# ControlModule.net
KiCad netlist of a schematic drawn in EAGLE
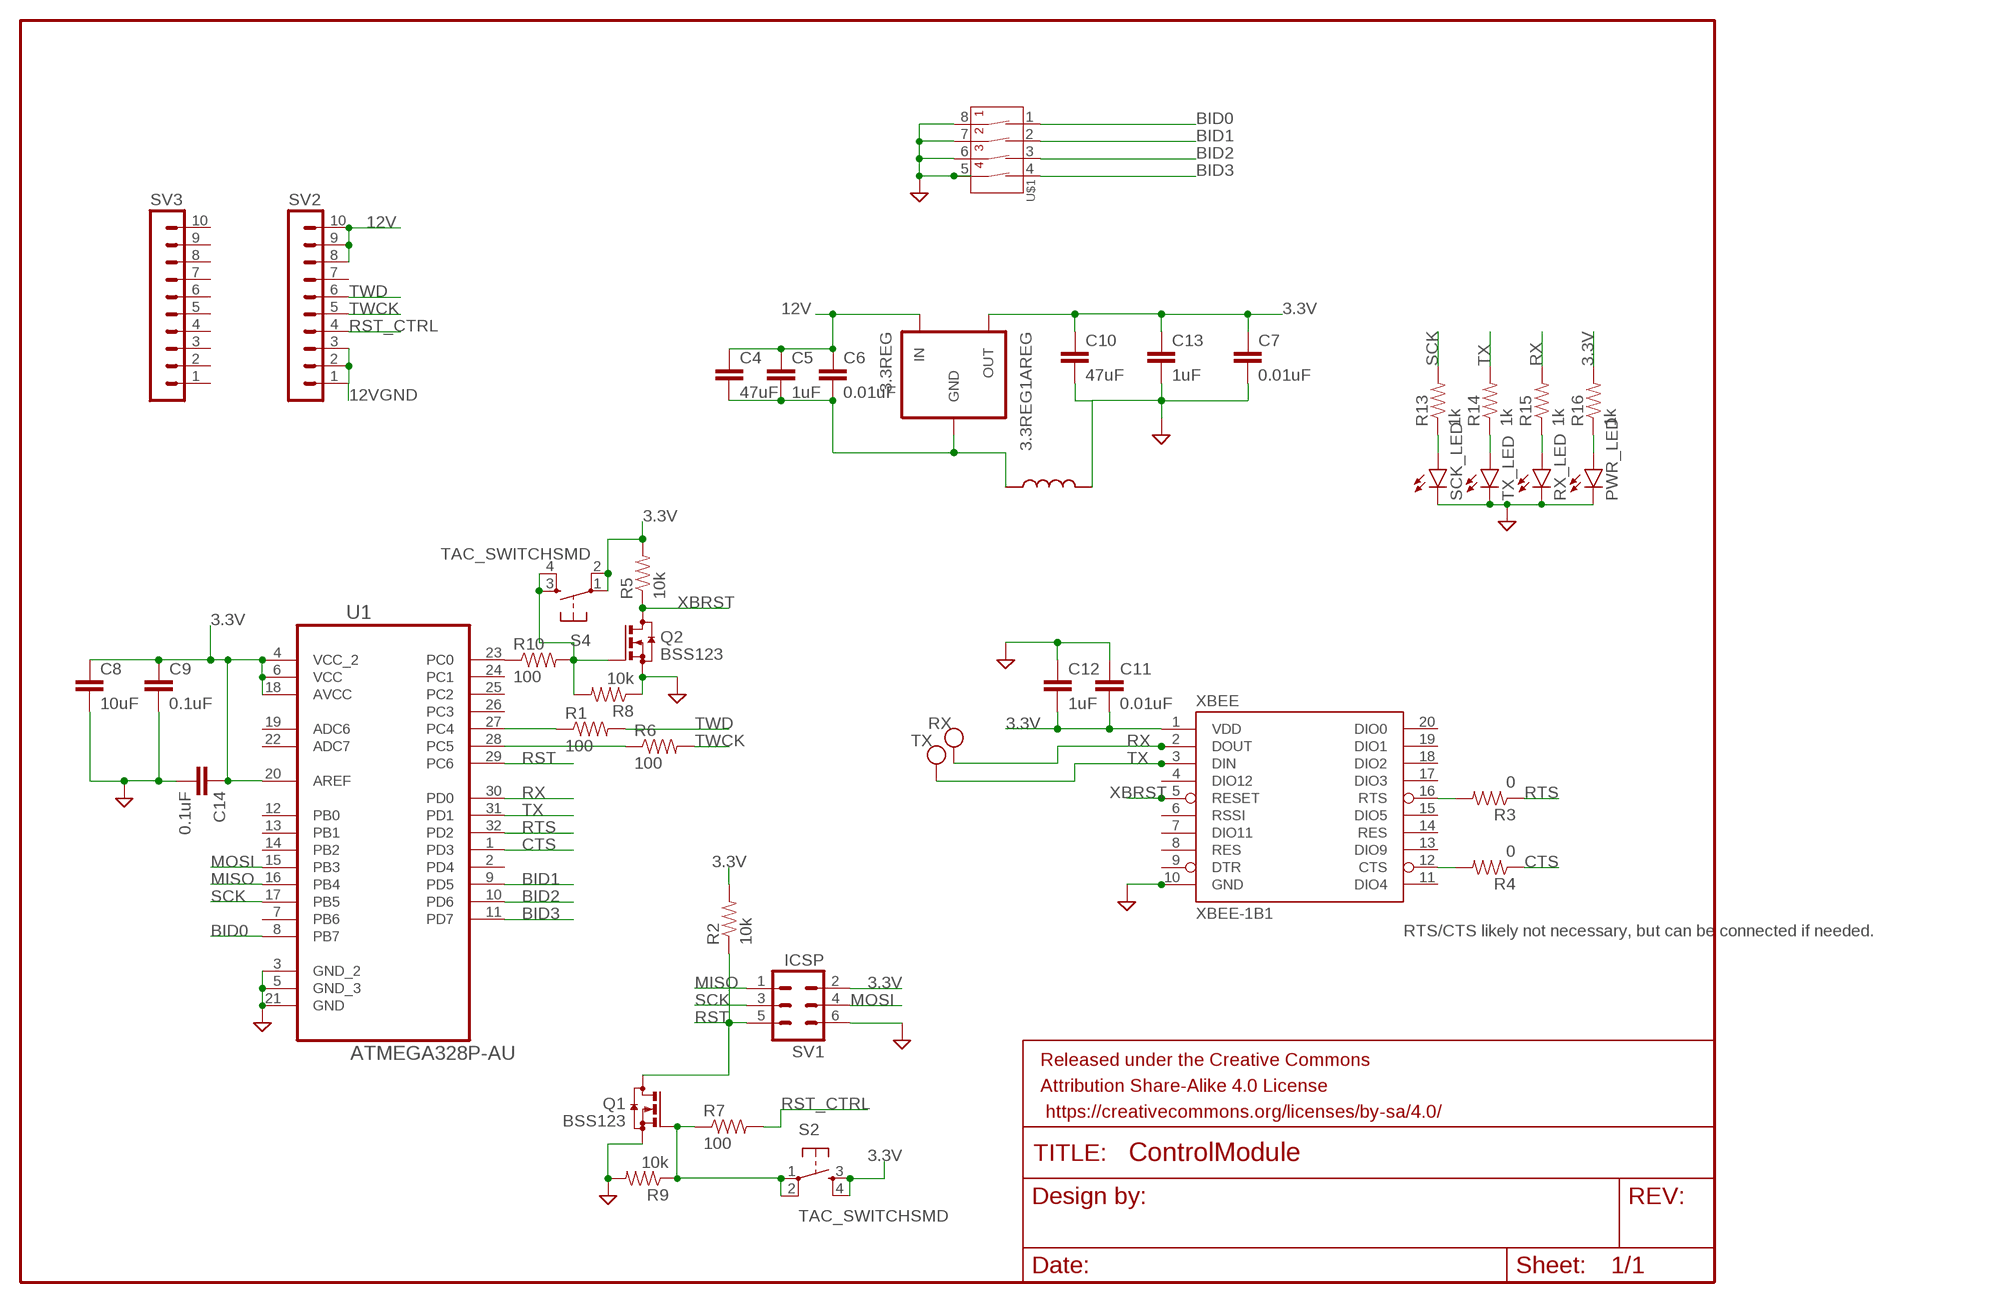
[diagram p0: schematic, sheet 1]

(export (version "E")
  (design (tool "Eeschema 10.0.6"))
  (components
    (comp (ref "3.3REG")
      (value "3.3REG1AREG")
      (footprint "eagle-import:DPAK")
      (libsource (lib "eagle-import") (part "3.3REG1AREG"))
    )
    (comp (ref "C4")
      (value "47uF")
      (footprint "eagle-import:1206")
      (libsource (lib "eagle-import") (part "CAP1206"))
    )
    (comp (ref "C5")
      (value "1uF")
      (footprint "eagle-import:0805")
      (libsource (lib "eagle-import") (part "CAP0805"))
    )
    (comp (ref "C6")
      (value "0.01uF")
      (footprint "eagle-import:0805")
      (libsource (lib "eagle-import") (part "CAP0805"))
    )
    (comp (ref "C7")
      (value "0.01uF")
      (footprint "eagle-import:0805")
      (libsource (lib "eagle-import") (part "CAP0805"))
    )
    (comp (ref "C8")
      (value "10uF")
      (footprint "eagle-import:0805")
      (libsource (lib "eagle-import") (part "CAP0805"))
    )
    (comp (ref "C9")
      (value "0.1uF")
      (footprint "eagle-import:0805")
      (libsource (lib "eagle-import") (part "CAP0805"))
    )
    (comp (ref "C10")
      (value "47uF")
      (footprint "eagle-import:1206")
      (libsource (lib "eagle-import") (part "CAP1206"))
    )
    (comp (ref "C11")
      (value "0.01uF")
      (footprint "eagle-import:0805")
      (libsource (lib "eagle-import") (part "CAP0805"))
    )
    (comp (ref "C12")
      (value "1uF")
      (footprint "eagle-import:0805")
      (libsource (lib "eagle-import") (part "CAP0805"))
    )
    (comp (ref "C13")
      (value "1uF")
      (footprint "eagle-import:0805")
      (libsource (lib "eagle-import") (part "CAP0805"))
    )
    (comp (ref "C14")
      (value "0.1uF")
      (footprint "eagle-import:0805")
      (libsource (lib "eagle-import") (part "CAP0805"))
    )
    (comp (ref "FRAME1")
      (value "FRAME-LETTER")
      (footprint "eagle-import:CREATIVE_COMMONS")
      (libsource (lib "eagle-import") (part "FRAME-LETTER"))
    )
    (comp (ref "PWR_LED")
      (value "LED1206")
      (footprint "eagle-import:LED-1206")
      (libsource (lib "eagle-import") (part "LED1206"))
    )
    (comp (ref "Q1")
      (value "BSS123")
      (footprint "eagle-import:SOT23")
      (libsource (lib "eagle-import") (part "BSS123"))
    )
    (comp (ref "Q2")
      (value "BSS123")
      (footprint "eagle-import:SOT23")
      (libsource (lib "eagle-import") (part "BSS123"))
    )
    (comp (ref "R1")
      (value "100")
      (footprint "eagle-import:0805")
      (libsource (lib "eagle-import") (part "RESISTOR0805-RES"))
    )
    (comp (ref "R2")
      (value "10k")
      (footprint "eagle-import:0805")
      (libsource (lib "eagle-import") (part "RESISTOR0805-RES"))
    )
    (comp (ref "R3")
      (value "0")
      (footprint "eagle-import:0805")
      (libsource (lib "eagle-import") (part "RESISTOR0805-RES"))
    )
    (comp (ref "R4")
      (value "0")
      (footprint "eagle-import:0805")
      (libsource (lib "eagle-import") (part "RESISTOR0805-RES"))
    )
    (comp (ref "R5")
      (value "10k")
      (footprint "eagle-import:0805")
      (libsource (lib "eagle-import") (part "RESISTOR0805-RES"))
    )
    (comp (ref "R6")
      (value "100")
      (footprint "eagle-import:0805")
      (libsource (lib "eagle-import") (part "RESISTOR0805-RES"))
    )
    (comp (ref "R7")
      (value "100")
      (footprint "eagle-import:0805")
      (libsource (lib "eagle-import") (part "RESISTOR0805-RES"))
    )
    (comp (ref "R8")
      (value "10k")
      (footprint "eagle-import:0805")
      (libsource (lib "eagle-import") (part "RESISTOR0805-RES"))
    )
    (comp (ref "R9")
      (value "10k")
      (footprint "eagle-import:0805")
      (libsource (lib "eagle-import") (part "RESISTOR0805-RES"))
    )
    (comp (ref "R10")
      (value "100")
      (footprint "eagle-import:0805")
      (libsource (lib "eagle-import") (part "RESISTOR0805-RES"))
    )
    (comp (ref "R13")
      (value "1k")
      (footprint "eagle-import:0805")
      (libsource (lib "eagle-import") (part "RESISTOR0805-RES"))
    )
    (comp (ref "R14")
      (value "1k")
      (footprint "eagle-import:0805")
      (libsource (lib "eagle-import") (part "RESISTOR0805-RES"))
    )
    (comp (ref "R15")
      (value "1k")
      (footprint "eagle-import:0805")
      (libsource (lib "eagle-import") (part "RESISTOR0805-RES"))
    )
    (comp (ref "R16")
      (value "1k")
      (footprint "eagle-import:0805")
      (libsource (lib "eagle-import") (part "RESISTOR0805-RES"))
    )
    (comp (ref "RX")
      (value "TEST_PT")
      (footprint "eagle-import:TESTING_PT")
      (libsource (lib "eagle-import") (part "TEST_PT"))
    )
    (comp (ref "RX_LED")
      (value "LED1206")
      (footprint "eagle-import:LED-1206")
      (libsource (lib "eagle-import") (part "LED1206"))
    )
    (comp (ref "S2")
      (value "TAC_SWITCHSMD")
      (footprint "eagle-import:TACTILE-SWITCH-SMD")
      (libsource (lib "eagle-import") (part "TAC_SWITCHSMD"))
    )
    (comp (ref "S4")
      (value "TAC_SWITCHSMD")
      (footprint "eagle-import:TACTILE-SWITCH-SMD")
      (libsource (lib "eagle-import") (part "TAC_SWITCHSMD"))
    )
    (comp (ref "SCK_LED")
      (value "LED1206")
      (footprint "eagle-import:LED-1206")
      (libsource (lib "eagle-import") (part "LED1206"))
    )
    (comp (ref "SV1")
      (value "ICSP")
      (footprint "eagle-import:MA03-2")
      (libsource (lib "eagle-import") (part "MA03-2"))
    )
    (comp (ref "SV2")
      (value "MA10-1W")
      (footprint "eagle-import:MA10-1W")
      (libsource (lib "eagle-import") (part "MA10-1W"))
    )
    (comp (ref "SV3")
      (value "MA10-1W")
      (footprint "eagle-import:MA10-1W")
      (libsource (lib "eagle-import") (part "MA10-1W"))
    )
    (comp (ref "TX")
      (value "TEST_PT")
      (footprint "eagle-import:TESTING_PT")
      (libsource (lib "eagle-import") (part "TEST_PT"))
    )
    (comp (ref "TX_LED")
      (value "LED1206")
      (footprint "eagle-import:LED-1206")
      (libsource (lib "eagle-import") (part "LED1206"))
    )
    (comp (ref "U$1")
      (value "4-POS-DIP")
      (footprint "eagle-import:4-POS-DIP-SMD")
      (libsource (lib "eagle-import") (part "4-POS-DIP"))
    )
    (comp (ref "U$2")
      (value "INDUCTOR")
      (footprint "eagle-import:0805")
      (libsource (lib "eagle-import") (part "INDUCTOR"))
    )
    (comp (ref "U1")
      (value "ATMEGA328P-AU")
      (footprint "eagle-import:QFP80P900X900X120-32N")
      (libsource (lib "eagle-import") (part "ATMEGA328P-AU"))
    )
    (comp (ref "XBEE")
      (value "XBEE-1B1")
      (footprint "eagle-import:XBEE-1")
      (libsource (lib "eagle-import") (part "XBEE-1B1"))
    )
  )
  (nets
    (net (code "1") (name "/3.3V") (class "Default")
      (node (ref "3.3REG") (pin "SOURCE") (pinfunction "OUT_SOURCE") (pintype "bidirectional"))
      (node (ref "C10") (pin "1") (pinfunction "1_1") (pintype "passive"))
      (node (ref "C11") (pin "2") (pinfunction "2_2") (pintype "passive"))
      (node (ref "C12") (pin "2") (pinfunction "2_2") (pintype "passive"))
      (node (ref "C13") (pin "1") (pinfunction "1_1") (pintype "passive"))
      (node (ref "C14") (pin "1") (pinfunction "1_1") (pintype "passive"))
      (node (ref "C7") (pin "1") (pinfunction "1_1") (pintype "passive"))
      (node (ref "C8") (pin "1") (pinfunction "1_1") (pintype "passive"))
      (node (ref "C9") (pin "1") (pinfunction "1_1") (pintype "passive"))
      (node (ref "R16") (pin "2") (pinfunction "2_2") (pintype "passive"))
      (node (ref "R2") (pin "2") (pinfunction "2_2") (pintype "passive"))
      (node (ref "R5") (pin "2") (pinfunction "2_2") (pintype "passive"))
      (node (ref "S2") (pin "3") (pinfunction "3_3") (pintype "passive"))
      (node (ref "S2") (pin "4") (pinfunction "4_4") (pintype "passive"))
      (node (ref "S4") (pin "1") (pinfunction "1_1") (pintype "passive"))
      (node (ref "S4") (pin "2") (pinfunction "2_2") (pintype "passive"))
      (node (ref "SV1") (pin "2") (pinfunction "2_2") (pintype "passive"))
      (node (ref "U1") (pin "18") (pinfunction "AVCC_18") (pintype "power_in"))
      (node (ref "U1") (pin "20") (pinfunction "AREF_20") (pintype "input"))
      (node (ref "U1") (pin "4") (pinfunction "VCC_2_4") (pintype "power_in"))
      (node (ref "U1") (pin "6") (pinfunction "VCC_6") (pintype "power_in"))
      (node (ref "XBEE") (pin "1") (pinfunction "VDD_1") (pintype "power_in"))
    )
    (net (code "2") (name "/12V") (class "Default")
      (node (ref "3.3REG") (pin "GATE") (pinfunction "IN_GATE") (pintype "input"))
      (node (ref "C4") (pin "1") (pinfunction "1_1") (pintype "passive"))
      (node (ref "C5") (pin "1") (pinfunction "1_1") (pintype "passive"))
      (node (ref "C6") (pin "1") (pinfunction "1_1") (pintype "passive"))
      (node (ref "SV2") (pin "10") (pinfunction "10_10") (pintype "passive"))
      (node (ref "SV2") (pin "8") (pinfunction "8_8") (pintype "passive"))
      (node (ref "SV2") (pin "9") (pinfunction "9_9") (pintype "passive"))
    )
    (net (code "3") (name "/12VGND") (class "Default")
      (node (ref "3.3REG") (pin "DRAIN") (pinfunction "GND_DRAIN") (pintype "bidirectional"))
      (node (ref "C4") (pin "2") (pinfunction "2_2") (pintype "passive"))
      (node (ref "C5") (pin "2") (pinfunction "2_2") (pintype "passive"))
      (node (ref "C6") (pin "2") (pinfunction "2_2") (pintype "passive"))
      (node (ref "SV2") (pin "1") (pinfunction "1_1") (pintype "passive"))
      (node (ref "SV2") (pin "2") (pinfunction "2_2") (pintype "passive"))
      (node (ref "SV2") (pin "3") (pinfunction "3_3") (pintype "passive"))
      (node (ref "U$2") (pin "1") (pinfunction "P$1_1") (pintype "bidirectional"))
    )
    (net (code "4") (name "/BID0") (class "Default")
      (node (ref "U$1") (pin "1") (pinfunction "1A_1") (pintype "bidirectional"))
      (node (ref "U1") (pin "8") (pinfunction "PB7_8") (pintype "bidirectional"))
    )
    (net (code "5") (name "/BID1") (class "Default")
      (node (ref "U$1") (pin "2") (pinfunction "2A_2") (pintype "bidirectional"))
      (node (ref "U1") (pin "9") (pinfunction "PD5_9") (pintype "bidirectional"))
    )
    (net (code "6") (name "/BID2") (class "Default")
      (node (ref "U$1") (pin "3") (pinfunction "3A_3") (pintype "bidirectional"))
      (node (ref "U1") (pin "10") (pinfunction "PD6_10") (pintype "bidirectional"))
    )
    (net (code "7") (name "/BID3") (class "Default")
      (node (ref "U$1") (pin "4") (pinfunction "4A_4") (pintype "bidirectional"))
      (node (ref "U1") (pin "11") (pinfunction "PD7_11") (pintype "bidirectional"))
    )
    (net (code "8") (name "/CTS") (class "Default")
      (node (ref "R4") (pin "1") (pinfunction "1_1") (pintype "passive"))
      (node (ref "U1") (pin "1") (pinfunction "PD3_1") (pintype "bidirectional"))
    )
    (net (code "9") (name "/MISO") (class "Default")
      (node (ref "SV1") (pin "1") (pinfunction "1_1") (pintype "passive"))
      (node (ref "U1") (pin "16") (pinfunction "PB4_16") (pintype "bidirectional"))
    )
    (net (code "10") (name "/MOSI") (class "Default")
      (node (ref "SV1") (pin "4") (pinfunction "4_4") (pintype "passive"))
      (node (ref "U1") (pin "15") (pinfunction "PB3_15") (pintype "bidirectional"))
    )
    (net (code "11") (name "/RST") (class "Default")
      (node (ref "Q1") (pin "3") (pinfunction "D_3") (pintype "passive"))
      (node (ref "R2") (pin "1") (pinfunction "1_1") (pintype "passive"))
      (node (ref "SV1") (pin "5") (pinfunction "5_5") (pintype "passive"))
      (node (ref "U1") (pin "29") (pinfunction "PC6_29") (pintype "bidirectional"))
    )
    (net (code "12") (name "/RST_CTRL") (class "Default")
      (node (ref "R7") (pin "2") (pinfunction "2_2") (pintype "passive"))
      (node (ref "SV2") (pin "4") (pinfunction "4_4") (pintype "passive"))
    )
    (net (code "13") (name "/RTS") (class "Default")
      (node (ref "R3") (pin "1") (pinfunction "1_1") (pintype "passive"))
      (node (ref "U1") (pin "32") (pinfunction "PD2_32") (pintype "bidirectional"))
    )
    (net (code "14") (name "/RX") (class "Default")
      (node (ref "R15") (pin "2") (pinfunction "2_2") (pintype "passive"))
      (node (ref "RX") (pin "P$1") (pinfunction "P$1_P$1") (pintype "bidirectional"))
      (node (ref "U1") (pin "30") (pinfunction "PD0_30") (pintype "bidirectional"))
      (node (ref "XBEE") (pin "2") (pinfunction "DOUT_2") (pintype "output"))
    )
    (net (code "15") (name "/SCK") (class "Default")
      (node (ref "R13") (pin "2") (pinfunction "2_2") (pintype "passive"))
      (node (ref "SV1") (pin "3") (pinfunction "3_3") (pintype "passive"))
      (node (ref "U1") (pin "17") (pinfunction "PB5_17") (pintype "bidirectional"))
    )
    (net (code "16") (name "/TWCK") (class "Default")
      (node (ref "R6") (pin "2") (pinfunction "2_2") (pintype "passive"))
      (node (ref "SV2") (pin "5") (pinfunction "5_5") (pintype "passive"))
    )
    (net (code "17") (name "/TWD") (class "Default")
      (node (ref "R1") (pin "2") (pinfunction "2_2") (pintype "passive"))
      (node (ref "SV2") (pin "6") (pinfunction "6_6") (pintype "passive"))
    )
    (net (code "18") (name "/TX") (class "Default")
      (node (ref "R14") (pin "2") (pinfunction "2_2") (pintype "passive"))
      (node (ref "TX") (pin "P$1") (pinfunction "P$1_P$1") (pintype "bidirectional"))
      (node (ref "U1") (pin "31") (pinfunction "PD1_31") (pintype "bidirectional"))
      (node (ref "XBEE") (pin "3") (pinfunction "DIN_3") (pintype "input"))
    )
    (net (code "19") (name "/XBRST") (class "Default")
      (node (ref "Q2") (pin "3") (pinfunction "D_3") (pintype "passive"))
      (node (ref "R5") (pin "1") (pinfunction "1_1") (pintype "passive"))
      (node (ref "XBEE") (pin "5") (pinfunction "RESET_5") (pintype "input"))
    )
    (net (code "20") (name "GND") (class "Default")
      (node (ref "C10") (pin "2") (pinfunction "2_2") (pintype "passive"))
      (node (ref "C11") (pin "1") (pinfunction "1_1") (pintype "passive"))
      (node (ref "C12") (pin "1") (pinfunction "1_1") (pintype "passive"))
      (node (ref "C13") (pin "2") (pinfunction "2_2") (pintype "passive"))
      (node (ref "C14") (pin "2") (pinfunction "2_2") (pintype "passive"))
      (node (ref "C7") (pin "2") (pinfunction "2_2") (pintype "passive"))
      (node (ref "C8") (pin "2") (pinfunction "2_2") (pintype "passive"))
      (node (ref "C9") (pin "2") (pinfunction "2_2") (pintype "passive"))
      (node (ref "PWR_LED") (pin "C") (pinfunction "C_C") (pintype "passive"))
      (node (ref "Q1") (pin "2") (pinfunction "S_2") (pintype "passive"))
      (node (ref "Q2") (pin "2") (pinfunction "S_2") (pintype "passive"))
      (node (ref "R8") (pin "1") (pinfunction "1_1") (pintype "passive"))
      (node (ref "R9") (pin "2") (pinfunction "2_2") (pintype "passive"))
      (node (ref "RX_LED") (pin "C") (pinfunction "C_C") (pintype "passive"))
      (node (ref "SCK_LED") (pin "C") (pinfunction "C_C") (pintype "passive"))
      (node (ref "SV1") (pin "6") (pinfunction "6_6") (pintype "passive"))
      (node (ref "TX_LED") (pin "C") (pinfunction "C_C") (pintype "passive"))
      (node (ref "U$1") (pin "5") (pinfunction "4B_5") (pintype "bidirectional"))
      (node (ref "U$1") (pin "6") (pinfunction "3B_6") (pintype "bidirectional"))
      (node (ref "U$1") (pin "7") (pinfunction "2B_7") (pintype "bidirectional"))
      (node (ref "U$1") (pin "8") (pinfunction "1B_8") (pintype "bidirectional"))
      (node (ref "U$2") (pin "2") (pinfunction "P$2_2") (pintype "bidirectional"))
      (node (ref "U1") (pin "21") (pinfunction "GND_21") (pintype "passive"))
      (node (ref "U1") (pin "3") (pinfunction "GND_2_3") (pintype "passive"))
      (node (ref "U1") (pin "5") (pinfunction "GND_3_5") (pintype "passive"))
      (node (ref "XBEE") (pin "10") (pinfunction "GND_10") (pintype "power_in"))
    )
    (net (code "21") (name "Net-(PWR_LED-PadA)") (class "Default")
      (node (ref "PWR_LED") (pin "A") (pinfunction "A_A") (pintype "passive"))
      (node (ref "R16") (pin "1") (pinfunction "1_1") (pintype "passive"))
    )
    (net (code "22") (name "Net-(Q1-G)") (class "Default")
      (node (ref "Q1") (pin "1") (pinfunction "G_1") (pintype "passive"))
      (node (ref "R7") (pin "1") (pinfunction "1_1") (pintype "passive"))
      (node (ref "R9") (pin "1") (pinfunction "1_1") (pintype "passive"))
      (node (ref "S2") (pin "1") (pinfunction "1_1") (pintype "passive"))
      (node (ref "S2") (pin "2") (pinfunction "2_2") (pintype "passive"))
    )
    (net (code "23") (name "Net-(Q2-G)") (class "Default")
      (node (ref "Q2") (pin "1") (pinfunction "G_1") (pintype "passive"))
      (node (ref "R10") (pin "2") (pinfunction "2_2") (pintype "passive"))
      (node (ref "R8") (pin "2") (pinfunction "2_2") (pintype "passive"))
      (node (ref "S4") (pin "3") (pinfunction "3_3") (pintype "passive"))
      (node (ref "S4") (pin "4") (pinfunction "4_4") (pintype "passive"))
    )
    (net (code "24") (name "Net-(R13-Pad1)") (class "Default")
      (node (ref "R13") (pin "1") (pinfunction "1_1") (pintype "passive"))
      (node (ref "SCK_LED") (pin "A") (pinfunction "A_A") (pintype "passive"))
    )
    (net (code "25") (name "Net-(R14-Pad1)") (class "Default")
      (node (ref "R14") (pin "1") (pinfunction "1_1") (pintype "passive"))
      (node (ref "TX_LED") (pin "A") (pinfunction "A_A") (pintype "passive"))
    )
    (net (code "26") (name "Net-(R15-Pad1)") (class "Default")
      (node (ref "R15") (pin "1") (pinfunction "1_1") (pintype "passive"))
      (node (ref "RX_LED") (pin "A") (pinfunction "A_A") (pintype "passive"))
    )
    (net (code "27") (name "Net-(U1-PC0)") (class "Default")
      (node (ref "R10") (pin "1") (pinfunction "1_1") (pintype "passive"))
      (node (ref "U1") (pin "23") (pinfunction "PC0_23") (pintype "bidirectional"))
    )
    (net (code "28") (name "Net-(U1-PC4)") (class "Default")
      (node (ref "R1") (pin "1") (pinfunction "1_1") (pintype "passive"))
      (node (ref "U1") (pin "27") (pinfunction "PC4_27") (pintype "bidirectional"))
    )
    (net (code "29") (name "Net-(U1-PC5)") (class "Default")
      (node (ref "R6") (pin "1") (pinfunction "1_1") (pintype "passive"))
      (node (ref "U1") (pin "28") (pinfunction "PC5_28") (pintype "bidirectional"))
    )
    (net (code "30") (name "Net-(XBEE-CTS)") (class "Default")
      (node (ref "R4") (pin "2") (pinfunction "2_2") (pintype "passive"))
      (node (ref "XBEE") (pin "12") (pinfunction "CTS_12") (pintype "output"))
    )
    (net (code "31") (name "Net-(XBEE-RTS)") (class "Default")
      (node (ref "R3") (pin "2") (pinfunction "2_2") (pintype "passive"))
      (node (ref "XBEE") (pin "16") (pinfunction "RTS_16") (pintype "input"))
    )
    (net (code "32") (name "unconnected-(SV2-Pad7)") (class "Default")
      (node (ref "SV2") (pin "7") (pinfunction "7_7") (pintype "passive"))
    )
    (net (code "33") (name "unconnected-(SV3-Pad1)") (class "Default")
      (node (ref "SV3") (pin "1") (pinfunction "1_1") (pintype "passive"))
    )
    (net (code "34") (name "unconnected-(SV3-Pad2)") (class "Default")
      (node (ref "SV3") (pin "2") (pinfunction "2_2") (pintype "passive"))
    )
    (net (code "35") (name "unconnected-(SV3-Pad3)") (class "Default")
      (node (ref "SV3") (pin "3") (pinfunction "3_3") (pintype "passive"))
    )
    (net (code "36") (name "unconnected-(SV3-Pad4)") (class "Default")
      (node (ref "SV3") (pin "4") (pinfunction "4_4") (pintype "passive"))
    )
    (net (code "37") (name "unconnected-(SV3-Pad5)") (class "Default")
      (node (ref "SV3") (pin "5") (pinfunction "5_5") (pintype "passive"))
    )
    (net (code "38") (name "unconnected-(SV3-Pad6)") (class "Default")
      (node (ref "SV3") (pin "6") (pinfunction "6_6") (pintype "passive"))
    )
    (net (code "39") (name "unconnected-(SV3-Pad7)") (class "Default")
      (node (ref "SV3") (pin "7") (pinfunction "7_7") (pintype "passive"))
    )
    (net (code "40") (name "unconnected-(SV3-Pad8)") (class "Default")
      (node (ref "SV3") (pin "8") (pinfunction "8_8") (pintype "passive"))
    )
    (net (code "41") (name "unconnected-(SV3-Pad9)") (class "Default")
      (node (ref "SV3") (pin "9") (pinfunction "9_9") (pintype "passive"))
    )
    (net (code "42") (name "unconnected-(SV3-Pad10)") (class "Default")
      (node (ref "SV3") (pin "10") (pinfunction "10_10") (pintype "passive"))
    )
    (net (code "43") (name "unconnected-(U1-ADC6-Pad19)") (class "Default")
      (node (ref "U1") (pin "19") (pinfunction "ADC6_19") (pintype "input"))
    )
    (net (code "44") (name "unconnected-(U1-ADC7-Pad22)") (class "Default")
      (node (ref "U1") (pin "22") (pinfunction "ADC7_22") (pintype "input"))
    )
    (net (code "45") (name "unconnected-(U1-PB0-Pad12)") (class "Default")
      (node (ref "U1") (pin "12") (pinfunction "PB0_12") (pintype "bidirectional"))
    )
    (net (code "46") (name "unconnected-(U1-PB1-Pad13)") (class "Default")
      (node (ref "U1") (pin "13") (pinfunction "PB1_13") (pintype "bidirectional"))
    )
    (net (code "47") (name "unconnected-(U1-PB2-Pad14)") (class "Default")
      (node (ref "U1") (pin "14") (pinfunction "PB2_14") (pintype "bidirectional"))
    )
    (net (code "48") (name "unconnected-(U1-PB6-Pad7)") (class "Default")
      (node (ref "U1") (pin "7") (pinfunction "PB6_7") (pintype "bidirectional"))
    )
    (net (code "49") (name "unconnected-(U1-PC1-Pad24)") (class "Default")
      (node (ref "U1") (pin "24") (pinfunction "PC1_24") (pintype "bidirectional"))
    )
    (net (code "50") (name "unconnected-(U1-PC2-Pad25)") (class "Default")
      (node (ref "U1") (pin "25") (pinfunction "PC2_25") (pintype "bidirectional"))
    )
    (net (code "51") (name "unconnected-(U1-PC3-Pad26)") (class "Default")
      (node (ref "U1") (pin "26") (pinfunction "PC3_26") (pintype "bidirectional"))
    )
    (net (code "52") (name "unconnected-(U1-PD4-Pad2)") (class "Default")
      (node (ref "U1") (pin "2") (pinfunction "PD4_2") (pintype "bidirectional"))
    )
    (net (code "53") (name "unconnected-(XBEE-DIO0-Pad20)") (class "Default")
      (node (ref "XBEE") (pin "20") (pinfunction "DIO0_20") (pintype "bidirectional"))
    )
    (net (code "54") (name "unconnected-(XBEE-DIO1-Pad19)") (class "Default")
      (node (ref "XBEE") (pin "19") (pinfunction "DIO1_19") (pintype "bidirectional"))
    )
    (net (code "55") (name "unconnected-(XBEE-DIO2-Pad18)") (class "Default")
      (node (ref "XBEE") (pin "18") (pinfunction "DIO2_18") (pintype "bidirectional"))
    )
    (net (code "56") (name "unconnected-(XBEE-DIO3-Pad17)") (class "Default")
      (node (ref "XBEE") (pin "17") (pinfunction "DIO3_17") (pintype "bidirectional"))
    )
    (net (code "57") (name "unconnected-(XBEE-DIO4-Pad11)") (class "Default")
      (node (ref "XBEE") (pin "11") (pinfunction "DIO4_11") (pintype "bidirectional"))
    )
    (net (code "58") (name "unconnected-(XBEE-DIO5-Pad15)") (class "Default")
      (node (ref "XBEE") (pin "15") (pinfunction "DIO5_15") (pintype "bidirectional"))
    )
    (net (code "59") (name "unconnected-(XBEE-DIO9-Pad13)") (class "Default")
      (node (ref "XBEE") (pin "13") (pinfunction "DIO9_13") (pintype "bidirectional"))
    )
    (net (code "60") (name "unconnected-(XBEE-DIO11-Pad7)") (class "Default")
      (node (ref "XBEE") (pin "7") (pinfunction "DIO11_7") (pintype "bidirectional"))
    )
    (net (code "61") (name "unconnected-(XBEE-DIO12-Pad4)") (class "Default")
      (node (ref "XBEE") (pin "4") (pinfunction "DIO12_4") (pintype "bidirectional"))
    )
    (net (code "62") (name "unconnected-(XBEE-DTR-Pad9)") (class "Default")
      (node (ref "XBEE") (pin "9") (pinfunction "DTR_9") (pintype "bidirectional"))
    )
    (net (code "63") (name "unconnected-(XBEE-RES-Pad8)") (class "Default")
      (node (ref "XBEE") (pin "8") (pinfunction "RES_8") (pintype "bidirectional"))
    )
    (net (code "64") (name "unconnected-(XBEE-RES-Pad14)") (class "Default")
      (node (ref "XBEE") (pin "14") (pinfunction "RES_14") (pintype "bidirectional"))
    )
    (net (code "65") (name "unconnected-(XBEE-RSSI-Pad6)") (class "Default")
      (node (ref "XBEE") (pin "6") (pinfunction "RSSI_6") (pintype "bidirectional"))
    )
  )
)
